# LeoPhiv4.net
KiCad netlist of a schematic drawn in EAGLE
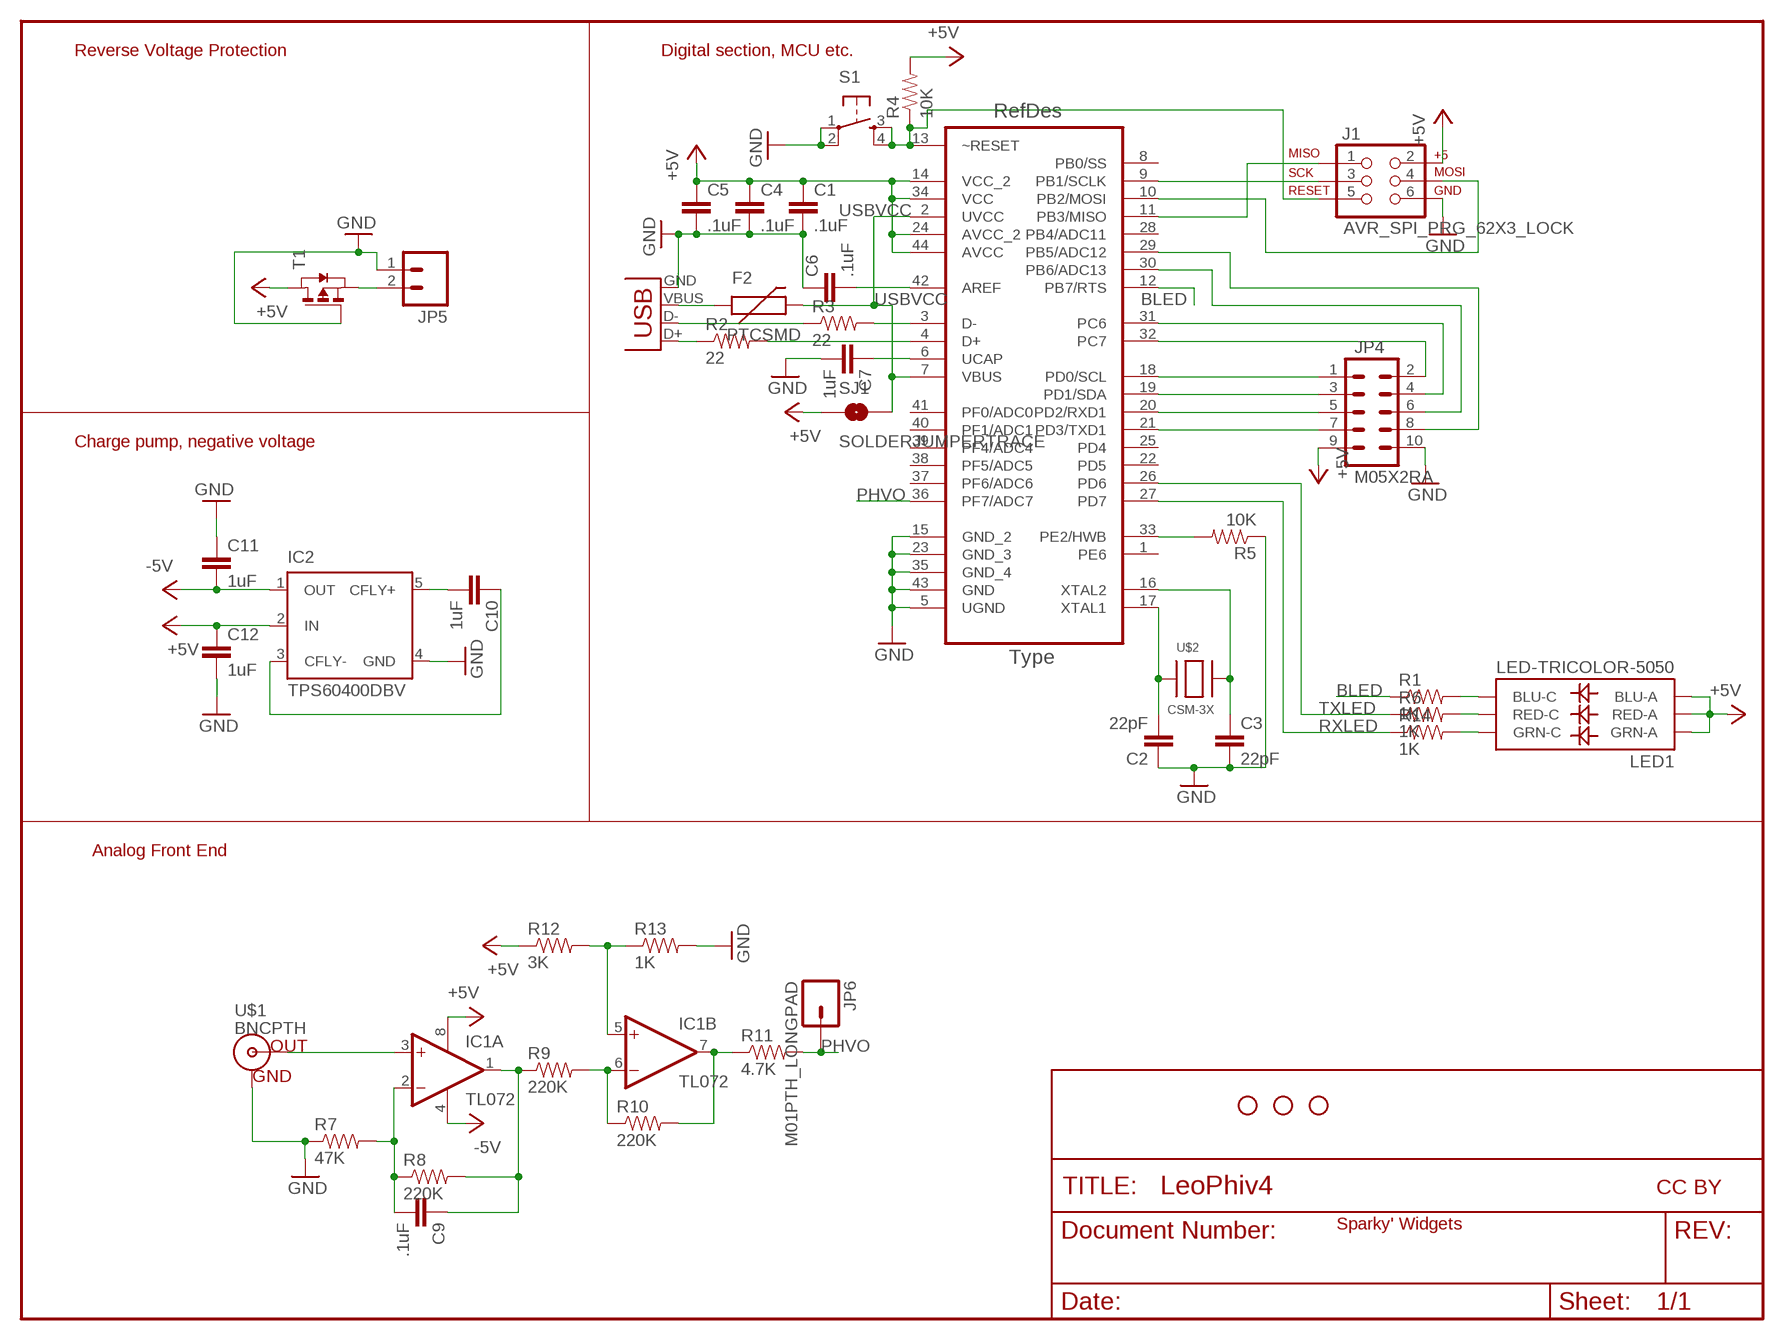
[diagram p0: schematic, sheet 1]

(export (version "E")
  (design (tool "Eeschema 10.0.6"))
  (components
    (comp (ref "C1")
      (value ".1uF")
      (footprint "eagle-import:0805")
      (libsource (lib "eagle-import") (part "CAP0805"))
    )
    (comp (ref "C2")
      (value "22pF")
      (footprint "eagle-import:0805")
      (libsource (lib "eagle-import") (part "CAP0805"))
    )
    (comp (ref "C3")
      (value "22pF")
      (footprint "eagle-import:0805")
      (libsource (lib "eagle-import") (part "CAP0805"))
    )
    (comp (ref "C4")
      (value ".1uF")
      (footprint "eagle-import:0805")
      (libsource (lib "eagle-import") (part "CAP0805"))
    )
    (comp (ref "C5")
      (value ".1uF")
      (footprint "eagle-import:0805")
      (libsource (lib "eagle-import") (part "CAP0805"))
    )
    (comp (ref "C6")
      (value ".1uF")
      (footprint "eagle-import:0805")
      (libsource (lib "eagle-import") (part "CAP0805"))
    )
    (comp (ref "C7")
      (value "1uF")
      (footprint "eagle-import:0805")
      (libsource (lib "eagle-import") (part "CAP0805"))
    )
    (comp (ref "C9")
      (value ".1uF")
      (footprint "eagle-import:0805")
      (libsource (lib "eagle-import") (part "CAP0805"))
    )
    (comp (ref "C10")
      (value "1uF")
      (footprint "eagle-import:0805")
      (libsource (lib "eagle-import") (part "CAP0805"))
    )
    (comp (ref "C11")
      (value "1uF")
      (footprint "eagle-import:0805")
      (libsource (lib "eagle-import") (part "CAP0805"))
    )
    (comp (ref "C12")
      (value "1uF")
      (footprint "eagle-import:0805")
      (libsource (lib "eagle-import") (part "CAP0805"))
    )
    (comp (ref "F2")
      (value "PTCSMD")
      (footprint "eagle-import:PTC-1206")
      (libsource (lib "eagle-import") (part "PTCSMD"))
    )
    (comp (ref "IC1")
      (value "TL072")
      (footprint "eagle-import:SO08")
      (libsource (lib "eagle-import") (part "LM358D"))
    )
    (comp (ref "IC2")
      (value "TPS60400DBV")
      (footprint "eagle-import:SOT23-DBV")
      (libsource (lib "eagle-import") (part "TPS60400DBV"))
    )
    (comp (ref "J1")
      (value "AVR_SPI_PRG_62X3_LOCK")
      (footprint "eagle-import:2X3_LOCK")
      (libsource (lib "eagle-import") (part "AVR_SPI_PRG_62X3_LOCK"))
    )
    (comp (ref "JP1")
      (value "STAND-OFF")
      (footprint "eagle-import:STAND-OFF")
      (libsource (lib "eagle-import") (part "STAND-OFF"))
    )
    (comp (ref "JP2")
      (value "STAND-OFF")
      (footprint "eagle-import:STAND-OFF")
      (libsource (lib "eagle-import") (part "STAND-OFF"))
    )
    (comp (ref "JP3")
      (value "STAND-OFF")
      (footprint "eagle-import:STAND-OFF")
      (libsource (lib "eagle-import") (part "STAND-OFF"))
    )
    (comp (ref "JP4")
      (value "M05X2RA")
      (footprint "eagle-import:2X5-RA")
      (libsource (lib "eagle-import") (part "M05X2RA"))
    )
    (comp (ref "JP5")
      (value "M02POLAR")
      (footprint "eagle-import:MOLEX-1X2")
      (libsource (lib "eagle-import") (part "M02POLAR"))
    )
    (comp (ref "JP6")
      (value "M01PTH_LONGPAD")
      (footprint "eagle-import:1X01_LONGPAD")
      (libsource (lib "eagle-import") (part "M01PTH_LONGPAD"))
    )
    (comp (ref "LED1")
      (value "LED-TRICOLOR-5050")
      (footprint "eagle-import:LED-TRICOLOR-5050")
      (libsource (lib "eagle-import") (part "LED-TRICOLOR-5050"))
    )
    (comp (ref "R1")
      (value "1K")
      (footprint "eagle-import:0805")
      (libsource (lib "eagle-import") (part "RESISTOR0805-RES"))
    )
    (comp (ref "R2")
      (value "22")
      (footprint "eagle-import:0805")
      (libsource (lib "eagle-import") (part "RESISTOR0805-RES"))
    )
    (comp (ref "R3")
      (value "22")
      (footprint "eagle-import:0805")
      (libsource (lib "eagle-import") (part "RESISTOR0805-RES"))
    )
    (comp (ref "R4")
      (value "10K")
      (footprint "eagle-import:0805")
      (libsource (lib "eagle-import") (part "RESISTOR0805-RES"))
    )
    (comp (ref "R5")
      (value "10K")
      (footprint "eagle-import:0805")
      (libsource (lib "eagle-import") (part "RESISTOR0805-RES"))
    )
    (comp (ref "R6")
      (value "1K")
      (footprint "eagle-import:0805")
      (libsource (lib "eagle-import") (part "RESISTOR0805-RES"))
    )
    (comp (ref "R7")
      (value "47K")
      (footprint "eagle-import:0805")
      (libsource (lib "eagle-import") (part "RESISTOR0805-RES"))
    )
    (comp (ref "R8")
      (value "220K")
      (footprint "eagle-import:0805")
      (libsource (lib "eagle-import") (part "RESISTOR0805-RES"))
    )
    (comp (ref "R9")
      (value "220K")
      (footprint "eagle-import:0805")
      (libsource (lib "eagle-import") (part "RESISTOR0805-RES"))
    )
    (comp (ref "R10")
      (value "220K")
      (footprint "eagle-import:0805")
      (libsource (lib "eagle-import") (part "RESISTOR0805-RES"))
    )
    (comp (ref "R11")
      (value "4.7K")
      (footprint "eagle-import:0805")
      (libsource (lib "eagle-import") (part "RESISTOR0805-RES"))
    )
    (comp (ref "R12")
      (value "3K")
      (footprint "eagle-import:0805")
      (libsource (lib "eagle-import") (part "RESISTOR0805-RES"))
    )
    (comp (ref "R13")
      (value "1K")
      (footprint "eagle-import:0805")
      (libsource (lib "eagle-import") (part "RESISTOR0805-RES"))
    )
    (comp (ref "R14")
      (value "1K")
      (footprint "eagle-import:0805")
      (libsource (lib "eagle-import") (part "RESISTOR0805-RES"))
    )
    (comp (ref "S1")
      (value "TAC_SWITCHSMD")
      (footprint "eagle-import:TACTILE_SWITCH_SMD")
      (libsource (lib "eagle-import") (part "TAC_SWITCHSMD"))
    )
    (comp (ref "SJ1")
      (value "SOLDERJUMPERTRACE")
      (footprint "eagle-import:SJ_2S-TRACE")
      (libsource (lib "eagle-import") (part "SOLDERJUMPERTRACE"))
    )
    (comp (ref "T1")
      (value "PMOSSOT23")
      (footprint "eagle-import:SOT-23")
      (libsource (lib "eagle-import") (part "PMOSSOT23"))
    )
    (comp (ref "U$1")
      (value "BNCPTH")
      (footprint "eagle-import:BNC")
      (libsource (lib "eagle-import") (part "BNCPTH"))
    )
    (comp (ref "U$2")
      (value "CSM-3X")
      (footprint "eagle-import:XTALCSM3X")
      (libsource (lib "eagle-import") (part "CSM-3X"))
    )
    (comp (ref "U1")
      (value "ATMEGA32U4-AU")
      (footprint "eagle-import:QFP80P1200X1200X120-44N")
      (libsource (lib "eagle-import") (part "ATMEGA32U4-AU"))
    )
    (comp (ref "X1")
      (value "USBSMD")
      (footprint "eagle-import:USB-MINIB")
      (libsource (lib "eagle-import") (part "USBSMD"))
    )
  )
  (nets
    (net (code "1") (name "+5V") (class "Default")
      (node (ref "C1") (pin "1") (pinfunction "1_1") (pintype "passive"))
      (node (ref "C12") (pin "1") (pinfunction "1_1") (pintype "passive"))
      (node (ref "C4") (pin "1") (pinfunction "1_1") (pintype "passive"))
      (node (ref "C5") (pin "1") (pinfunction "1_1") (pintype "passive"))
      (node (ref "IC1") (pin "8") (pinfunction "V+_8") (pintype "power_in"))
      (node (ref "IC2") (pin "2") (pinfunction "IN_2") (pintype "input"))
      (node (ref "J1") (pin "2") (pinfunction "2_2") (pintype "passive"))
      (node (ref "JP4") (pin "9") (pinfunction "9_9") (pintype "passive"))
      (node (ref "LED1") (pin "1") (pinfunction "GRN-A_1") (pintype "bidirectional"))
      (node (ref "LED1") (pin "2") (pinfunction "RED-A_2") (pintype "bidirectional"))
      (node (ref "LED1") (pin "3") (pinfunction "BLU-A_3") (pintype "bidirectional"))
      (node (ref "R12") (pin "1") (pinfunction "1_1") (pintype "passive"))
      (node (ref "R4") (pin "2") (pinfunction "2_2") (pintype "passive"))
      (node (ref "SJ1") (pin "1") (pinfunction "1_1") (pintype "passive"))
      (node (ref "T1") (pin "1") (pinfunction "D_1") (pintype "passive"))
      (node (ref "U1") (pin "14") (pinfunction "VCC_2_14") (pintype "power_in"))
      (node (ref "U1") (pin "24") (pinfunction "AVCC_2_24") (pintype "power_in"))
      (node (ref "U1") (pin "34") (pinfunction "VCC_34") (pintype "power_in"))
      (node (ref "U1") (pin "44") (pinfunction "AVCC_44") (pintype "power_in"))
    )
    (net (code "2") (name "-5V") (class "Default")
      (node (ref "C11") (pin "2") (pinfunction "2_2") (pintype "passive"))
      (node (ref "IC1") (pin "4") (pinfunction "V-_4") (pintype "power_in"))
      (node (ref "IC2") (pin "1") (pinfunction "OUT_1") (pintype "input"))
    )
    (net (code "3") (name "/BLED") (class "Default")
      (node (ref "R1") (pin "1") (pinfunction "1_1") (pintype "passive"))
      (node (ref "U1") (pin "12") (pinfunction "PB7/RTS_12") (pintype "bidirectional"))
    )
    (net (code "4") (name "/PHVO") (class "Default")
      (node (ref "JP6") (pin "1") (pinfunction "1_1") (pintype "passive"))
      (node (ref "R11") (pin "2") (pinfunction "2_2") (pintype "passive"))
      (node (ref "U1") (pin "36") (pinfunction "PF7/ADC7_36") (pintype "bidirectional"))
    )
    (net (code "5") (name "/RXLED") (class "Default")
      (node (ref "R14") (pin "1") (pinfunction "1_1") (pintype "passive"))
      (node (ref "U1") (pin "27") (pinfunction "PD7_27") (pintype "bidirectional"))
    )
    (net (code "6") (name "/TXLED") (class "Default")
      (node (ref "R6") (pin "1") (pinfunction "1_1") (pintype "passive"))
      (node (ref "U1") (pin "26") (pinfunction "PD6_26") (pintype "bidirectional"))
    )
    (net (code "7") (name "/USBVCC") (class "Default")
      (node (ref "F2") (pin "2") (pinfunction "2_2") (pintype "bidirectional"))
      (node (ref "SJ1") (pin "2") (pinfunction "2_2") (pintype "passive"))
      (node (ref "U1") (pin "2") (pinfunction "UVCC_2") (pintype "power_in"))
      (node (ref "U1") (pin "7") (pinfunction "VBUS_7") (pintype "input"))
    )
    (net (code "8") (name "GND") (class "Default")
      (node (ref "C1") (pin "2") (pinfunction "2_2") (pintype "passive"))
      (node (ref "C11") (pin "1") (pinfunction "1_1") (pintype "passive"))
      (node (ref "C12") (pin "2") (pinfunction "2_2") (pintype "passive"))
      (node (ref "C2") (pin "1") (pinfunction "1_1") (pintype "passive"))
      (node (ref "C3") (pin "2") (pinfunction "2_2") (pintype "passive"))
      (node (ref "C4") (pin "2") (pinfunction "2_2") (pintype "passive"))
      (node (ref "C5") (pin "2") (pinfunction "2_2") (pintype "passive"))
      (node (ref "C6") (pin "1") (pinfunction "1_1") (pintype "passive"))
      (node (ref "C7") (pin "2") (pinfunction "2_2") (pintype "passive"))
      (node (ref "IC2") (pin "4") (pinfunction "GND_4") (pintype "passive"))
      (node (ref "J1") (pin "6") (pinfunction "6_6") (pintype "passive"))
      (node (ref "JP4") (pin "10") (pinfunction "10_10") (pintype "passive"))
      (node (ref "JP5") (pin "1") (pinfunction "1_1") (pintype "passive"))
      (node (ref "R13") (pin "2") (pinfunction "2_2") (pintype "passive"))
      (node (ref "R5") (pin "1") (pinfunction "1_1") (pintype "passive"))
      (node (ref "R7") (pin "1") (pinfunction "1_1") (pintype "passive"))
      (node (ref "S1") (pin "1") (pinfunction "1_1") (pintype "passive"))
      (node (ref "S1") (pin "2") (pinfunction "2_2") (pintype "passive"))
      (node (ref "T1") (pin "3") (pinfunction "G_3") (pintype "passive"))
      (node (ref "U$1") (pin "GND") (pinfunction "GND_GND") (pintype "bidirectional"))
      (node (ref "U1") (pin "15") (pinfunction "GND_2_15") (pintype "passive"))
      (node (ref "U1") (pin "23") (pinfunction "GND_3_23") (pintype "passive"))
      (node (ref "U1") (pin "35") (pinfunction "GND_4_35") (pintype "passive"))
      (node (ref "U1") (pin "43") (pinfunction "GND_43") (pintype "passive"))
      (node (ref "U1") (pin "5") (pinfunction "UGND_5") (pintype "passive"))
      (node (ref "X1") (pin "GND") (pinfunction "GND_GND") (pintype "bidirectional"))
    )
    (net (code "9") (name "Net-(F2-Pad1)") (class "Default")
      (node (ref "F2") (pin "1") (pinfunction "1_1") (pintype "bidirectional"))
      (node (ref "X1") (pin "VBUS") (pinfunction "VBUS_VBUS") (pintype "bidirectional"))
    )
    (net (code "10") (name "Net-(IC1A-+IN)") (class "Default")
      (node (ref "IC1") (pin "3") (pinfunction "+IN_3") (pintype "input"))
      (node (ref "U$1") (pin "S") (pinfunction "OUT_S") (pintype "bidirectional"))
    )
    (net (code "11") (name "Net-(IC1A--IN)") (class "Default")
      (node (ref "C9") (pin "2") (pinfunction "2_2") (pintype "passive"))
      (node (ref "IC1") (pin "2") (pinfunction "-IN_2") (pintype "input"))
      (node (ref "R7") (pin "2") (pinfunction "2_2") (pintype "passive"))
      (node (ref "R8") (pin "1") (pinfunction "1_1") (pintype "passive"))
    )
    (net (code "12") (name "Net-(IC1A-OUT)") (class "Default")
      (node (ref "C9") (pin "1") (pinfunction "1_1") (pintype "passive"))
      (node (ref "IC1") (pin "1") (pinfunction "OUT_1") (pintype "output"))
      (node (ref "R8") (pin "2") (pinfunction "2_2") (pintype "passive"))
      (node (ref "R9") (pin "1") (pinfunction "1_1") (pintype "passive"))
    )
    (net (code "13") (name "Net-(IC1B-+IN)") (class "Default")
      (node (ref "IC1") (pin "5") (pinfunction "+IN_5") (pintype "input"))
      (node (ref "R12") (pin "2") (pinfunction "2_2") (pintype "passive"))
      (node (ref "R13") (pin "1") (pinfunction "1_1") (pintype "passive"))
    )
    (net (code "14") (name "Net-(IC1B--IN)") (class "Default")
      (node (ref "IC1") (pin "6") (pinfunction "-IN_6") (pintype "input"))
      (node (ref "R10") (pin "1") (pinfunction "1_1") (pintype "passive"))
      (node (ref "R9") (pin "2") (pinfunction "2_2") (pintype "passive"))
    )
    (net (code "15") (name "Net-(IC1B-OUT)") (class "Default")
      (node (ref "IC1") (pin "7") (pinfunction "OUT_7") (pintype "output"))
      (node (ref "R10") (pin "2") (pinfunction "2_2") (pintype "passive"))
      (node (ref "R11") (pin "1") (pinfunction "1_1") (pintype "passive"))
    )
    (net (code "16") (name "Net-(IC2-CFLY+)") (class "Default")
      (node (ref "C10") (pin "2") (pinfunction "2_2") (pintype "passive"))
      (node (ref "IC2") (pin "5") (pinfunction "CFLY+_5") (pintype "passive"))
    )
    (net (code "17") (name "Net-(IC2-CFLY-)") (class "Default")
      (node (ref "C10") (pin "1") (pinfunction "1_1") (pintype "passive"))
      (node (ref "IC2") (pin "3") (pinfunction "CFLY-_3") (pintype "power_in"))
    )
    (net (code "18") (name "Net-(LED1-BLU-C)") (class "Default")
      (node (ref "LED1") (pin "4") (pinfunction "BLU-C_4") (pintype "bidirectional"))
      (node (ref "R1") (pin "2") (pinfunction "2_2") (pintype "passive"))
    )
    (net (code "19") (name "Net-(LED1-GRN-C)") (class "Default")
      (node (ref "LED1") (pin "6") (pinfunction "GRN-C_6") (pintype "bidirectional"))
      (node (ref "R14") (pin "2") (pinfunction "2_2") (pintype "passive"))
    )
    (net (code "20") (name "Net-(LED1-RED-C)") (class "Default")
      (node (ref "LED1") (pin "5") (pinfunction "RED-C_5") (pintype "bidirectional"))
      (node (ref "R6") (pin "2") (pinfunction "2_2") (pintype "passive"))
    )
    (net (code "21") (name "Net-(R2-Pad1)") (class "Default")
      (node (ref "R2") (pin "1") (pinfunction "1_1") (pintype "passive"))
      (node (ref "X1") (pin "D+") (pinfunction "D+_D+") (pintype "bidirectional"))
    )
    (net (code "22") (name "Net-(R3-Pad1)") (class "Default")
      (node (ref "R3") (pin "1") (pinfunction "1_1") (pintype "passive"))
      (node (ref "X1") (pin "D-") (pinfunction "D-_D-") (pintype "bidirectional"))
    )
    (net (code "23") (name "Net-(T1-S)") (class "Default")
      (node (ref "JP5") (pin "2") (pinfunction "2_2") (pintype "passive"))
      (node (ref "T1") (pin "2") (pinfunction "S_2") (pintype "passive"))
    )
    (net (code "24") (name "Net-(U$2-P$1)") (class "Default")
      (node (ref "C2") (pin "2") (pinfunction "2_2") (pintype "passive"))
      (node (ref "U$2") (pin "1") (pinfunction "P$1_1") (pintype "bidirectional"))
      (node (ref "U1") (pin "17") (pinfunction "XTAL1_17") (pintype "input"))
    )
    (net (code "25") (name "Net-(U$2-P$2)") (class "Default")
      (node (ref "C3") (pin "1") (pinfunction "1_1") (pintype "passive"))
      (node (ref "U$2") (pin "2") (pinfunction "P$2_2") (pintype "bidirectional"))
      (node (ref "U1") (pin "16") (pinfunction "XTAL2_16") (pintype "output"))
    )
    (net (code "26") (name "Net-(U1-AREF)") (class "Default")
      (node (ref "C6") (pin "2") (pinfunction "2_2") (pintype "passive"))
      (node (ref "U1") (pin "42") (pinfunction "AREF_42") (pintype "input"))
    )
    (net (code "27") (name "Net-(U1-D+)") (class "Default")
      (node (ref "R2") (pin "2") (pinfunction "2_2") (pintype "passive"))
      (node (ref "U1") (pin "4") (pinfunction "D+_4") (pintype "passive"))
    )
    (net (code "28") (name "Net-(U1-D-)") (class "Default")
      (node (ref "R3") (pin "2") (pinfunction "2_2") (pintype "passive"))
      (node (ref "U1") (pin "3") (pinfunction "D-_3") (pintype "passive"))
    )
    (net (code "29") (name "Net-(U1-PB1{slash}SCLK)") (class "Default")
      (node (ref "J1") (pin "3") (pinfunction "3_3") (pintype "passive"))
      (node (ref "U1") (pin "9") (pinfunction "PB1/SCLK_9") (pintype "bidirectional"))
    )
    (net (code "30") (name "Net-(U1-PB2{slash}MOSI)") (class "Default")
      (node (ref "J1") (pin "4") (pinfunction "4_4") (pintype "passive"))
      (node (ref "U1") (pin "10") (pinfunction "PB2/MOSI_10") (pintype "bidirectional"))
    )
    (net (code "31") (name "Net-(U1-PB3{slash}MISO)") (class "Default")
      (node (ref "J1") (pin "1") (pinfunction "1_1") (pintype "passive"))
      (node (ref "U1") (pin "11") (pinfunction "PB3/MISO_11") (pintype "bidirectional"))
    )
    (net (code "32") (name "Net-(U1-PB5{slash}ADC12)") (class "Default")
      (node (ref "JP4") (pin "8") (pinfunction "8_8") (pintype "passive"))
      (node (ref "U1") (pin "29") (pinfunction "PB5/ADC12_29") (pintype "bidirectional"))
    )
    (net (code "33") (name "Net-(U1-PB6{slash}ADC13)") (class "Default")
      (node (ref "JP4") (pin "6") (pinfunction "6_6") (pintype "passive"))
      (node (ref "U1") (pin "30") (pinfunction "PB6/ADC13_30") (pintype "bidirectional"))
    )
    (net (code "34") (name "Net-(U1-PC6)") (class "Default")
      (node (ref "JP4") (pin "4") (pinfunction "4_4") (pintype "passive"))
      (node (ref "U1") (pin "31") (pinfunction "PC6_31") (pintype "bidirectional"))
    )
    (net (code "35") (name "Net-(U1-PC7)") (class "Default")
      (node (ref "JP4") (pin "2") (pinfunction "2_2") (pintype "passive"))
      (node (ref "U1") (pin "32") (pinfunction "PC7_32") (pintype "bidirectional"))
    )
    (net (code "36") (name "Net-(U1-PD0{slash}SCL)") (class "Default")
      (node (ref "JP4") (pin "1") (pinfunction "1_1") (pintype "passive"))
      (node (ref "U1") (pin "18") (pinfunction "PD0/SCL_18") (pintype "bidirectional"))
    )
    (net (code "37") (name "Net-(U1-PD1{slash}SDA)") (class "Default")
      (node (ref "JP4") (pin "3") (pinfunction "3_3") (pintype "passive"))
      (node (ref "U1") (pin "19") (pinfunction "PD1/SDA_19") (pintype "bidirectional"))
    )
    (net (code "38") (name "Net-(U1-PD2{slash}RXD1)") (class "Default")
      (node (ref "JP4") (pin "5") (pinfunction "5_5") (pintype "passive"))
      (node (ref "U1") (pin "20") (pinfunction "PD2/RXD1_20") (pintype "bidirectional"))
    )
    (net (code "39") (name "Net-(U1-PD3{slash}TXD1)") (class "Default")
      (node (ref "JP4") (pin "7") (pinfunction "7_7") (pintype "passive"))
      (node (ref "U1") (pin "21") (pinfunction "PD3/TXD1_21") (pintype "bidirectional"))
    )
    (net (code "40") (name "Net-(U1-PE2{slash}HWB)") (class "Default")
      (node (ref "R5") (pin "2") (pinfunction "2_2") (pintype "passive"))
      (node (ref "U1") (pin "33") (pinfunction "PE2/HWB_33") (pintype "bidirectional"))
    )
    (net (code "41") (name "Net-(U1-UCAP)") (class "Default")
      (node (ref "C7") (pin "1") (pinfunction "1_1") (pintype "passive"))
      (node (ref "U1") (pin "6") (pinfunction "UCAP_6") (pintype "power_in"))
    )
    (net (code "42") (name "Net-(U1-~{RESET})") (class "Default")
      (node (ref "J1") (pin "5") (pinfunction "5_5") (pintype "passive"))
      (node (ref "R4") (pin "1") (pinfunction "1_1") (pintype "passive"))
      (node (ref "S1") (pin "3") (pinfunction "3_3") (pintype "passive"))
      (node (ref "S1") (pin "4") (pinfunction "4_4") (pintype "passive"))
      (node (ref "U1") (pin "13") (pinfunction "~{RESET}_13") (pintype "input"))
    )
    (net (code "43") (name "unconnected-(U1-PB0{slash}SS-Pad8)") (class "Default")
      (node (ref "U1") (pin "8") (pinfunction "PB0/SS_8") (pintype "bidirectional"))
    )
    (net (code "44") (name "unconnected-(U1-PB4{slash}ADC11-Pad28)") (class "Default")
      (node (ref "U1") (pin "28") (pinfunction "PB4/ADC11_28") (pintype "bidirectional"))
    )
    (net (code "45") (name "unconnected-(U1-PD4-Pad25)") (class "Default")
      (node (ref "U1") (pin "25") (pinfunction "PD4_25") (pintype "bidirectional"))
    )
    (net (code "46") (name "unconnected-(U1-PD5-Pad22)") (class "Default")
      (node (ref "U1") (pin "22") (pinfunction "PD5_22") (pintype "bidirectional"))
    )
    (net (code "47") (name "unconnected-(U1-PE6-Pad1)") (class "Default")
      (node (ref "U1") (pin "1") (pinfunction "PE6_1") (pintype "bidirectional"))
    )
    (net (code "48") (name "unconnected-(U1-PF0{slash}ADC0-Pad41)") (class "Default")
      (node (ref "U1") (pin "41") (pinfunction "PF0/ADC0_41") (pintype "bidirectional"))
    )
    (net (code "49") (name "unconnected-(U1-PF1{slash}ADC1-Pad40)") (class "Default")
      (node (ref "U1") (pin "40") (pinfunction "PF1/ADC1_40") (pintype "bidirectional"))
    )
    (net (code "50") (name "unconnected-(U1-PF4{slash}ADC4-Pad39)") (class "Default")
      (node (ref "U1") (pin "39") (pinfunction "PF4/ADC4_39") (pintype "bidirectional"))
    )
    (net (code "51") (name "unconnected-(U1-PF5{slash}ADC5-Pad38)") (class "Default")
      (node (ref "U1") (pin "38") (pinfunction "PF5/ADC5_38") (pintype "bidirectional"))
    )
    (net (code "52") (name "unconnected-(U1-PF6{slash}ADC6-Pad37)") (class "Default")
      (node (ref "U1") (pin "37") (pinfunction "PF6/ADC6_37") (pintype "bidirectional"))
    )
  )
)
